# 5_non_volatile_memory.net
KiCad netlist of a schematic drawn in Altium Designer
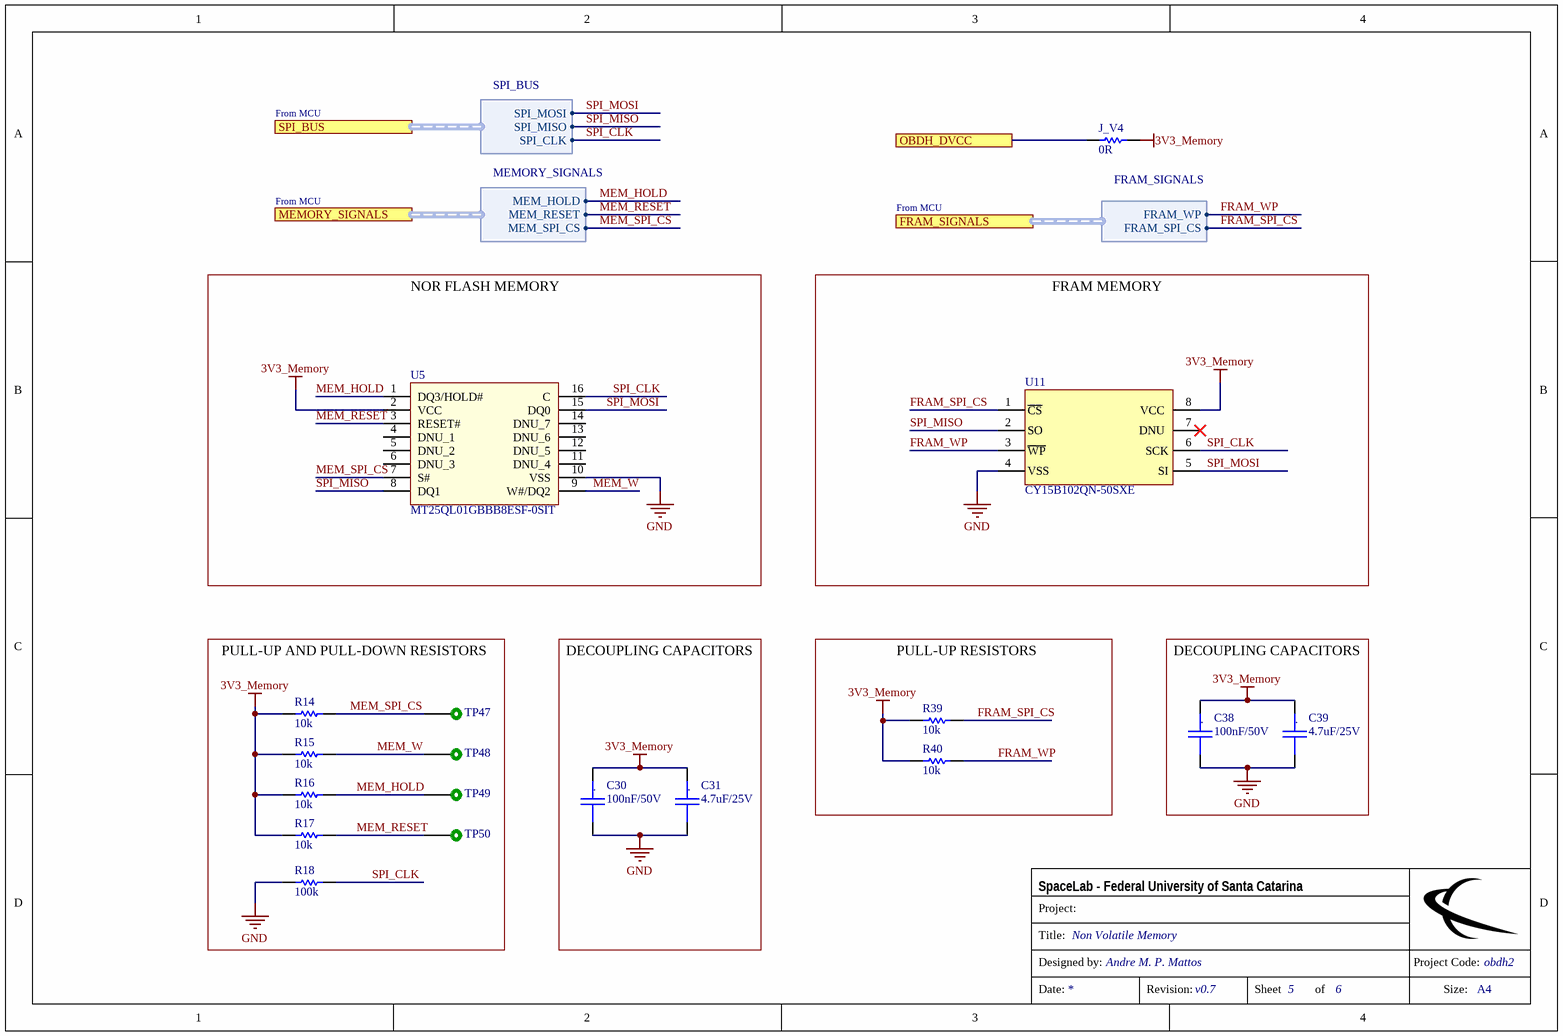
[diagram p0: 5_non_volatile_memory.schdoc]

(export (version "E")
  (design (tool "Eeschema 10.0.6"))
  (components
    (comp (ref "C30")
      (value "100nF/50V")
      (footprint "CC0805")
      (description "CAP CER 100nF 50V 0603 10%")
      (fields (field (name "PARTNUMBER") "C0603C104K5RAC3121"))
      (libsource (lib "schematics_library_legacy") (part "Cap_Cer_X7R_100nF_50V_0603"))
    )
    (comp (ref "C31")
      (value "4.7uF/25V")
      (footprint "CC0805")
      (description "CAP CER 4.7UF 25V 10% X7R 0805")
      (fields (field (name "PARTNUMBER") "C0805C475K3RACAUTO"))
      (libsource (lib "schematics_library_legacy") (part "Cap_Cer_X7R_4.7uF_25V_0805"))
    )
    (comp (ref "C38")
      (value "100nF/50V")
      (footprint "CC0805")
      (description "CAP CER 100nF 50V 0603 10%")
      (fields (field (name "PARTNUMBER") "C0603C104K5RAC3121"))
      (libsource (lib "schematics_library_legacy") (part "Cap_Cer_X7R_100nF_50V_0603"))
    )
    (comp (ref "C39")
      (value "4.7uF/25V")
      (footprint "CC0805")
      (description "CAP CER 4.7UF 25V 10% X7R 0805")
      (fields (field (name "PARTNUMBER") "C0805C475K3RACAUTO"))
      (libsource (lib "schematics_library_legacy") (part "Cap_Cer_X7R_4.7uF_25V_0805"))
    )
    (comp (ref "J_V4")
      (value "0R")
      (footprint "0805")
      (description "RES 0R OHM 1/8W JUMPER 0805")
      (fields (field (name "PARTNUMBER") "CRCW08050000Z0EA"))
      (libsource (lib "schematics_library_legacy") (part "R0R_JUMPER_1/8W_0805"))
    )
    (comp (ref "R14")
      (value "10k")
      (footprint "0805")
      (description "RES 10K OHM 1/8W 1%  0805")
      (fields (field (name "PARTNUMBER") "CRCW080510K0FKEA"))
      (libsource (lib "schematics_library_legacy") (part "R10k_1%_1/8W_0805"))
    )
    (comp (ref "R15")
      (value "10k")
      (footprint "0805")
      (description "RES 10K OHM 1/8W 1%  0805")
      (fields (field (name "PARTNUMBER") "CRCW080510K0FKEA"))
      (libsource (lib "schematics_library_legacy") (part "R10k_1%_1/8W_0805"))
    )
    (comp (ref "R16")
      (value "10k")
      (footprint "0805")
      (description "RES 10K OHM 1/8W 1%  0805")
      (fields (field (name "PARTNUMBER") "CRCW080510K0FKEA"))
      (libsource (lib "schematics_library_legacy") (part "R10k_1%_1/8W_0805"))
    )
    (comp (ref "R17")
      (value "10k")
      (footprint "0805")
      (description "RES 10K OHM 1/8W 1%  0805")
      (fields (field (name "PARTNUMBER") "CRCW080510K0FKEA"))
      (libsource (lib "schematics_library_legacy") (part "R10k_1%_1/8W_0805"))
    )
    (comp (ref "R18")
      (value "100k")
      (footprint "0805")
      (description "RES 100K OHM 1/8W 1% 0805")
      (fields (field (name "PARTNUMBER") "AC0805FR-13100KL"))
      (libsource (lib "schematics_library_legacy") (part "R100k_1%_1/8W_0805"))
    )
    (comp (ref "R39")
      (value "10k")
      (footprint "0805")
      (description "RES 10K OHM 1/8W 1%  0805")
      (fields (field (name "PARTNUMBER") "CRCW080510K0FKEA"))
      (libsource (lib "schematics_library_legacy") (part "R10k_1%_1/8W_0805"))
    )
    (comp (ref "R40")
      (value "10k")
      (footprint "0805")
      (description "RES 10K OHM 1/8W 1%  0805")
      (fields (field (name "PARTNUMBER") "CRCW080510K0FKEA"))
      (libsource (lib "schematics_library_legacy") (part "R10k_1%_1/8W_0805"))
    )
    (comp (ref "TP47")
      (value "TEST_POINT_2")
      (footprint "TEST_POINT_2")
      (description "Test point")
      (libsource (lib "OBDH_Eng_Model_2_ALT") (part "TEST_POINT_2"))
    )
    (comp (ref "TP48")
      (value "TEST_POINT_2")
      (footprint "TEST_POINT_2")
      (description "Test point")
      (libsource (lib "OBDH_Eng_Model_2_ALT") (part "TEST_POINT_2"))
    )
    (comp (ref "TP49")
      (value "TEST_POINT_2")
      (footprint "TEST_POINT_2")
      (description "Test point")
      (libsource (lib "OBDH_Eng_Model_2_ALT") (part "TEST_POINT_2"))
    )
    (comp (ref "TP50")
      (value "TEST_POINT_2")
      (footprint "TEST_POINT_2")
      (description "Test point")
      (libsource (lib "OBDH_Eng_Model_2_ALT") (part "TEST_POINT_2"))
    )
    (comp (ref "U5")
      (value "MT25QL01GBBB8ESF-0SIT")
      (footprint "SOIC127P1032X265-16N")
      (description "IC FLASH 1GBIT 108MHZ 16SOIC")
      (fields (field (name "MOUSER PART NUMBER") "340-278808-TRAY"))
      (libsource (lib "OBDH_Eng_Model_2_ALT") (part "MT25QL01GBBB8ESF-0SIT"))
    )
    (comp (ref "U11")
      (value "CY15B102QN-50SXE")
      (footprint "SOIC8")
      (description "FRAM (Ferroelectric RAM) Memory IC 2Mb (256K x 8) SPI 50 MHz 8-SOIC")
      (libsource (lib "schematics_library_legacy") (part "CY15B102QN-50SXE"))
    )
  )
  (nets
    (net (code "5") (name "/FRAM_SPI_CS") (class "Default")
      (node (ref "R39") (pin "1") (pinfunction "1_1") (pintype "passive"))
      (node (ref "U11") (pin "1") (pinfunction "~{CS}_1") (pintype "passive"))
    )
    (net (code "6") (name "/FRAM_WP") (class "Default")
      (node (ref "R40") (pin "1") (pinfunction "1_1") (pintype "passive"))
      (node (ref "U11") (pin "3") (pinfunction "~{WP}_3") (pintype "passive"))
    )
    (net (code "7") (name "/MEM_HOLD") (class "Default")
      (node (ref "R16") (pin "1") (pinfunction "1_1") (pintype "passive"))
      (node (ref "TP49") (pin "1") (pinfunction "1_1") (pintype "passive"))
      (node (ref "U5") (pin "1") (pinfunction "DQ3/HOLD#_1") (pintype "passive"))
    )
    (net (code "8") (name "/MEM_RESET") (class "Default")
      (node (ref "R17") (pin "1") (pinfunction "1_1") (pintype "passive"))
      (node (ref "TP50") (pin "1") (pinfunction "1_1") (pintype "passive"))
      (node (ref "U5") (pin "3") (pinfunction "RESET#_3") (pintype "passive"))
    )
    (net (code "9") (name "/MEM_SPI_CS") (class "Default")
      (node (ref "R14") (pin "1") (pinfunction "1_1") (pintype "passive"))
      (node (ref "TP47") (pin "1") (pinfunction "1_1") (pintype "passive"))
      (node (ref "U5") (pin "7") (pinfunction "S#_7") (pintype "passive"))
    )
    (net (code "10") (name "/MEM_W") (class "Default")
      (node (ref "R15") (pin "1") (pinfunction "1_1") (pintype "passive"))
      (node (ref "TP48") (pin "1") (pinfunction "1_1") (pintype "passive"))
      (node (ref "U5") (pin "9") (pinfunction "W#/DQ2_9") (pintype "passive"))
    )
    (net (code "11") (name "/OBDH_DVCC") (class "Default")
      (node (ref "J_V4") (pin "2") (pinfunction "2_2") (pintype "passive"))
    )
    (net (code "12") (name "/SPI_CLK") (class "Default")
      (node (ref "R18") (pin "1") (pinfunction "1_1") (pintype "passive"))
      (node (ref "U11") (pin "6") (pinfunction "SCK_6") (pintype "passive"))
      (node (ref "U5") (pin "16") (pinfunction "C_16") (pintype "passive"))
    )
    (net (code "13") (name "/SPI_MISO") (class "Default")
      (node (ref "U11") (pin "2") (pinfunction "SO_2") (pintype "passive"))
      (node (ref "U5") (pin "8") (pinfunction "DQ1_8") (pintype "passive"))
    )
    (net (code "14") (name "/SPI_MOSI") (class "Default")
      (node (ref "U11") (pin "5") (pinfunction "SI_5") (pintype "passive"))
      (node (ref "U5") (pin "15") (pinfunction "DQ0_15") (pintype "passive"))
    )
    (net (code "18") (name "3V3_Memory") (class "Default")
      (node (ref "C30") (pin "1") (pinfunction "1_1") (pintype "passive"))
      (node (ref "C31") (pin "1") (pinfunction "1_1") (pintype "passive"))
      (node (ref "C38") (pin "1") (pinfunction "1_1") (pintype "passive"))
      (node (ref "C39") (pin "1") (pinfunction "1_1") (pintype "passive"))
      (node (ref "J_V4") (pin "1") (pinfunction "1_1") (pintype "passive"))
      (node (ref "R14") (pin "2") (pinfunction "2_2") (pintype "passive"))
      (node (ref "R15") (pin "2") (pinfunction "2_2") (pintype "passive"))
      (node (ref "R16") (pin "2") (pinfunction "2_2") (pintype "passive"))
      (node (ref "R17") (pin "2") (pinfunction "2_2") (pintype "passive"))
      (node (ref "R39") (pin "2") (pinfunction "2_2") (pintype "passive"))
      (node (ref "R40") (pin "2") (pinfunction "2_2") (pintype "passive"))
      (node (ref "U11") (pin "8") (pinfunction "VCC_8") (pintype "power_in"))
      (node (ref "U5") (pin "2") (pinfunction "VCC_2") (pintype "passive"))
    )
    (net (code "19") (name "GND") (class "Default")
      (node (ref "C30") (pin "2") (pinfunction "2_2") (pintype "passive"))
      (node (ref "C31") (pin "2") (pinfunction "2_2") (pintype "passive"))
      (node (ref "C38") (pin "2") (pinfunction "2_2") (pintype "passive"))
      (node (ref "C39") (pin "2") (pinfunction "2_2") (pintype "passive"))
      (node (ref "R18") (pin "2") (pinfunction "2_2") (pintype "passive"))
      (node (ref "U11") (pin "4") (pinfunction "VSS_4") (pintype "passive"))
      (node (ref "U5") (pin "10") (pinfunction "VSS_10") (pintype "passive"))
    )
    (net (code "20") (name "unconnected-(U5-DNU_1-Pad4)") (class "Default")
      (node (ref "U5") (pin "4") (pinfunction "DNU_1_4") (pintype "passive"))
    )
    (net (code "21") (name "unconnected-(U5-DNU_2-Pad5)") (class "Default")
      (node (ref "U5") (pin "5") (pinfunction "DNU_2_5") (pintype "passive"))
    )
    (net (code "22") (name "unconnected-(U5-DNU_3-Pad6)") (class "Default")
      (node (ref "U5") (pin "6") (pinfunction "DNU_3_6") (pintype "passive"))
    )
    (net (code "23") (name "unconnected-(U5-DNU_4-Pad11)") (class "Default")
      (node (ref "U5") (pin "11") (pinfunction "DNU_4_11") (pintype "passive"))
    )
    (net (code "24") (name "unconnected-(U5-DNU_5-Pad12)") (class "Default")
      (node (ref "U5") (pin "12") (pinfunction "DNU_5_12") (pintype "passive"))
    )
    (net (code "25") (name "unconnected-(U5-DNU_6-Pad13)") (class "Default")
      (node (ref "U5") (pin "13") (pinfunction "DNU_6_13") (pintype "passive"))
    )
    (net (code "26") (name "unconnected-(U5-DNU_7-Pad14)") (class "Default")
      (node (ref "U5") (pin "14") (pinfunction "DNU_7_14") (pintype "passive"))
    )
    (net (code "27") (name "unconnected-(U11-DNU-Pad7)") (class "Default")
      (node (ref "U11") (pin "7") (pinfunction "DNU_7") (pintype "passive+no_connect"))
    )
  )
)
